# Remote_Controller.net
KiCad netlist of a schematic drawn in Altium Designer
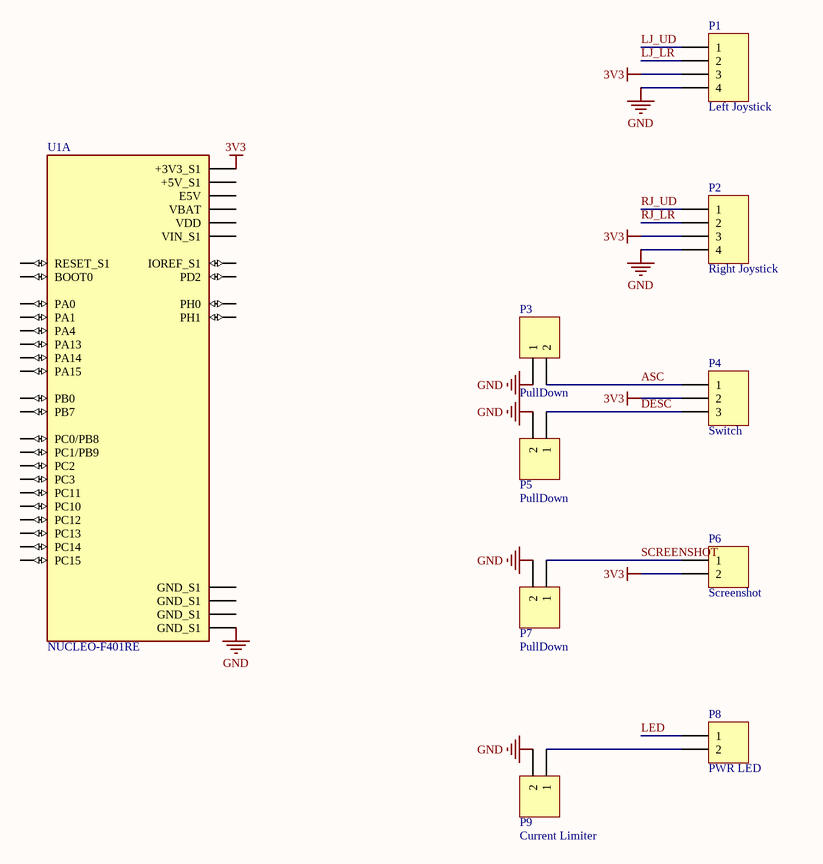
[diagram p0: Remote_Controller.SchDoc]

(export (version "E")
  (design (tool "Eeschema 10.0.6"))
  (components
    (comp (ref "P1")
      (value "Left Joystick")
      (footprint "HDR1X4")
      (description "Header, 4-Pin")
      (fields (field (name "PUBLISHER") "Altium Limited"))
      (libsource (lib "Miscellaneous Connectors") (part "Header 4"))
    )
    (comp (ref "P2")
      (value "Right Joystick")
      (footprint "HDR1X4")
      (description "Header, 4-Pin")
      (fields (field (name "PUBLISHER") "Altium Limited"))
      (libsource (lib "Miscellaneous Connectors") (part "Header 4"))
    )
    (comp (ref "P3")
      (value "PullDown")
      (footprint "HDR1X2")
      (description "Header, 2-Pin")
      (fields (field (name "PUBLISHER") "Altium Limited"))
      (libsource (lib "Miscellaneous Connectors") (part "Header 2"))
    )
    (comp (ref "P4")
      (value "Switch")
      (footprint "HDR1X3")
      (description "Header, 3-Pin")
      (fields (field (name "PUBLISHER") "Altium Limited"))
      (libsource (lib "Miscellaneous Connectors") (part "Header 3"))
    )
    (comp (ref "P5")
      (value "PullDown")
      (footprint "HDR1X2")
      (description "Header, 2-Pin")
      (fields (field (name "PUBLISHER") "Altium Limited"))
      (libsource (lib "") (part "Header 2_1"))
    )
    (comp (ref "P6")
      (value "Screenshot")
      (footprint "HDR1X2")
      (description "Header, 2-Pin")
      (fields (field (name "PUBLISHER") "Altium Limited"))
      (libsource (lib "") (part "Header 2_2"))
    )
    (comp (ref "P7")
      (value "PullDown")
      (footprint "HDR1X2")
      (description "Header, 2-Pin")
      (fields (field (name "PUBLISHER") "Altium Limited"))
      (libsource (lib "") (part "Header 2_1"))
    )
    (comp (ref "P8")
      (value "PWR LED")
      (footprint "HDR1X2")
      (description "Header, 2-Pin")
      (fields (field (name "PUBLISHER") "Altium Limited"))
      (libsource (lib "") (part "Header 2_2"))
    )
    (comp (ref "P9")
      (value "Current Limiter")
      (footprint "HDR1X2")
      (description "Header, 2-Pin")
      (fields (field (name "PUBLISHER") "Altium Limited"))
      (libsource (lib "") (part "Header 2_1"))
    )
    (comp (ref "U1")
      (value "NUCLEO-F401RE")
      (footprint "ST_NUCLEO-F401RE")
      (libsource (lib "NUCLEO-F401RE") (part "NUCLEO-F401RE"))
    )
  )
  (nets
    (net (code "1") (name "/ASC") (class "Default")
      (node (ref "P3") (pin "2") (pinfunction "2_2") (pintype "passive"))
      (node (ref "P4") (pin "1") (pinfunction "1_1") (pintype "passive"))
    )
    (net (code "2") (name "/DESC") (class "Default")
      (node (ref "P4") (pin "3") (pinfunction "3_3") (pintype "passive"))
      (node (ref "P5") (pin "1") (pinfunction "1_1") (pintype "passive"))
    )
    (net (code "3") (name "/LED") (class "Default")
      (node (ref "P8") (pin "1") (pinfunction "1_1") (pintype "passive"))
    )
    (net (code "4") (name "/LJ_LR") (class "Default")
      (node (ref "P1") (pin "2") (pinfunction "2_2") (pintype "passive"))
    )
    (net (code "5") (name "/LJ_UD") (class "Default")
      (node (ref "P1") (pin "1") (pinfunction "1_1") (pintype "passive"))
    )
    (net (code "6") (name "/RJ_LR") (class "Default")
      (node (ref "P2") (pin "2") (pinfunction "2_2") (pintype "passive"))
    )
    (net (code "7") (name "/RJ_UD") (class "Default")
      (node (ref "P2") (pin "1") (pinfunction "1_1") (pintype "passive"))
    )
    (net (code "8") (name "/SCREENSHOT") (class "Default")
      (node (ref "P6") (pin "1") (pinfunction "1_1") (pintype "passive"))
      (node (ref "P7") (pin "1") (pinfunction "1_1") (pintype "passive"))
    )
    (net (code "9") (name "3V3") (class "Default")
      (node (ref "P1") (pin "3") (pinfunction "3_3") (pintype "passive"))
      (node (ref "P2") (pin "3") (pinfunction "3_3") (pintype "passive"))
      (node (ref "P4") (pin "2") (pinfunction "2_2") (pintype "passive"))
      (node (ref "P6") (pin "2") (pinfunction "2_2") (pintype "passive"))
      (node (ref "U1") (pin "CN7_16") (pinfunction "+3V3_S1_CN7_16") (pintype "power_in"))
    )
    (net (code "10") (name "GND") (class "Default")
      (node (ref "P1") (pin "4") (pinfunction "4_4") (pintype "passive"))
      (node (ref "P2") (pin "4") (pinfunction "4_4") (pintype "passive"))
      (node (ref "P3") (pin "1") (pinfunction "1_1") (pintype "passive"))
      (node (ref "P5") (pin "2") (pinfunction "2_2") (pintype "passive"))
      (node (ref "P7") (pin "2") (pinfunction "2_2") (pintype "passive"))
      (node (ref "P9") (pin "2") (pinfunction "2_2") (pintype "passive"))
      (node (ref "U1") (pin "CN7_22") (pinfunction "GND_S1_CN7_22") (pintype "power_in"))
    )
    (net (code "11") (name "Net-(P8-Pad2)") (class "Default")
      (node (ref "P8") (pin "2") (pinfunction "2_2") (pintype "passive"))
      (node (ref "P9") (pin "1") (pinfunction "1_1") (pintype "passive"))
    )
    (net (code "12") (name "unconnected-(U1A-+5V_S1-PadCN7_18)") (class "Default")
      (node (ref "U1") (pin "CN7_18") (pinfunction "+5V_S1_CN7_18") (pintype "power_in"))
    )
    (net (code "13") (name "unconnected-(U1A-BOOT0-PadCN7_7)") (class "Default")
      (node (ref "U1") (pin "CN7_7") (pinfunction "BOOT0_CN7_7") (pintype "bidirectional"))
    )
    (net (code "14") (name "unconnected-(U1A-E5V-PadCN7_6)") (class "Default")
      (node (ref "U1") (pin "CN7_6") (pinfunction "E5V_CN7_6") (pintype "power_in"))
    )
    (net (code "15") (name "unconnected-(U1A-GND_S1-PadCN7_8)") (class "Default")
      (node (ref "U1") (pin "CN7_8") (pinfunction "GND_S1_CN7_8") (pintype "power_in"))
    )
    (net (code "16") (name "unconnected-(U1A-GND_S1-PadCN7_19)") (class "Default")
      (node (ref "U1") (pin "CN7_19") (pinfunction "GND_S1_CN7_19") (pintype "power_in"))
    )
    (net (code "17") (name "unconnected-(U1A-GND_S1-PadCN7_20)") (class "Default")
      (node (ref "U1") (pin "CN7_20") (pinfunction "GND_S1_CN7_20") (pintype "power_in"))
    )
    (net (code "18") (name "unconnected-(U1A-IOREF_S1-PadCN7_12)") (class "Default")
      (node (ref "U1") (pin "CN7_12") (pinfunction "IOREF_S1_CN7_12") (pintype "bidirectional"))
    )
    (net (code "19") (name "unconnected-(U1A-PA0-PadCN7_28)") (class "Default")
      (node (ref "U1") (pin "CN7_28") (pinfunction "PA0_CN7_28") (pintype "bidirectional"))
    )
    (net (code "20") (name "unconnected-(U1A-PA1-PadCN7_30)") (class "Default")
      (node (ref "U1") (pin "CN7_30") (pinfunction "PA1_CN7_30") (pintype "bidirectional"))
    )
    (net (code "21") (name "unconnected-(U1A-PA4-PadCN7_32)") (class "Default")
      (node (ref "U1") (pin "CN7_32") (pinfunction "PA4_CN7_32") (pintype "bidirectional"))
    )
    (net (code "22") (name "unconnected-(U1A-PA13-PadCN7_13)") (class "Default")
      (node (ref "U1") (pin "CN7_13") (pinfunction "PA13_CN7_13") (pintype "bidirectional"))
    )
    (net (code "23") (name "unconnected-(U1A-PA14-PadCN7_15)") (class "Default")
      (node (ref "U1") (pin "CN7_15") (pinfunction "PA14_CN7_15") (pintype "bidirectional"))
    )
    (net (code "24") (name "unconnected-(U1A-PA15-PadCN7_17)") (class "Default")
      (node (ref "U1") (pin "CN7_17") (pinfunction "PA15_CN7_17") (pintype "bidirectional"))
    )
    (net (code "25") (name "unconnected-(U1A-PB0-PadCN7_34)") (class "Default")
      (node (ref "U1") (pin "CN7_34") (pinfunction "PB0_CN7_34") (pintype "bidirectional"))
    )
    (net (code "26") (name "unconnected-(U1A-PB7-PadCN7_21)") (class "Default")
      (node (ref "U1") (pin "CN7_21") (pinfunction "PB7_CN7_21") (pintype "bidirectional"))
    )
    (net (code "27") (name "unconnected-(U1A-PC0{slash}PB8-PadCN7_38)") (class "Default")
      (node (ref "U1") (pin "CN7_38") (pinfunction "PC0/PB8_CN7_38") (pintype "bidirectional"))
    )
    (net (code "28") (name "unconnected-(U1A-PC1{slash}PB9-PadCN7_36)") (class "Default")
      (node (ref "U1") (pin "CN7_36") (pinfunction "PC1/PB9_CN7_36") (pintype "bidirectional"))
    )
    (net (code "29") (name "unconnected-(U1A-PC2-PadCN7_35)") (class "Default")
      (node (ref "U1") (pin "CN7_35") (pinfunction "PC2_CN7_35") (pintype "bidirectional"))
    )
    (net (code "30") (name "unconnected-(U1A-PC3-PadCN7_37)") (class "Default")
      (node (ref "U1") (pin "CN7_37") (pinfunction "PC3_CN7_37") (pintype "bidirectional"))
    )
    (net (code "31") (name "unconnected-(U1A-PC10-PadCN7_1)") (class "Default")
      (node (ref "U1") (pin "CN7_1") (pinfunction "PC10_CN7_1") (pintype "bidirectional"))
    )
    (net (code "32") (name "unconnected-(U1A-PC11-PadCN7_2)") (class "Default")
      (node (ref "U1") (pin "CN7_2") (pinfunction "PC11_CN7_2") (pintype "bidirectional"))
    )
    (net (code "33") (name "unconnected-(U1A-PC12-PadCN7_3)") (class "Default")
      (node (ref "U1") (pin "CN7_3") (pinfunction "PC12_CN7_3") (pintype "bidirectional"))
    )
    (net (code "34") (name "unconnected-(U1A-PC13-PadCN7_23)") (class "Default")
      (node (ref "U1") (pin "CN7_23") (pinfunction "PC13_CN7_23") (pintype "bidirectional"))
    )
    (net (code "35") (name "unconnected-(U1A-PC14-PadCN7_25)") (class "Default")
      (node (ref "U1") (pin "CN7_25") (pinfunction "PC14_CN7_25") (pintype "bidirectional"))
    )
    (net (code "36") (name "unconnected-(U1A-PC15-PadCN7_27)") (class "Default")
      (node (ref "U1") (pin "CN7_27") (pinfunction "PC15_CN7_27") (pintype "bidirectional"))
    )
    (net (code "37") (name "unconnected-(U1A-PD2-PadCN7_4)") (class "Default")
      (node (ref "U1") (pin "CN7_4") (pinfunction "PD2_CN7_4") (pintype "bidirectional"))
    )
    (net (code "38") (name "unconnected-(U1A-PH0-PadCN7_29)") (class "Default")
      (node (ref "U1") (pin "CN7_29") (pinfunction "PH0_CN7_29") (pintype "bidirectional"))
    )
    (net (code "39") (name "unconnected-(U1A-PH1-PadCN7_31)") (class "Default")
      (node (ref "U1") (pin "CN7_31") (pinfunction "PH1_CN7_31") (pintype "bidirectional"))
    )
    (net (code "40") (name "unconnected-(U1A-RESET_S1-PadCN7_14)") (class "Default")
      (node (ref "U1") (pin "CN7_14") (pinfunction "RESET_S1_CN7_14") (pintype "bidirectional"))
    )
    (net (code "41") (name "unconnected-(U1A-VBAT-PadCN7_33)") (class "Default")
      (node (ref "U1") (pin "CN7_33") (pinfunction "VBAT_CN7_33") (pintype "power_in"))
    )
    (net (code "42") (name "unconnected-(U1A-VDD-PadCN7_5)") (class "Default")
      (node (ref "U1") (pin "CN7_5") (pinfunction "VDD_CN7_5") (pintype "power_in"))
    )
    (net (code "43") (name "unconnected-(U1A-VIN_S1-PadCN7_24)") (class "Default")
      (node (ref "U1") (pin "CN7_24") (pinfunction "VIN_S1_CN7_24") (pintype "power_in"))
    )
  )
)
